# buttonInput.net
KiCad netlist of a schematic drawn in Altium Designer
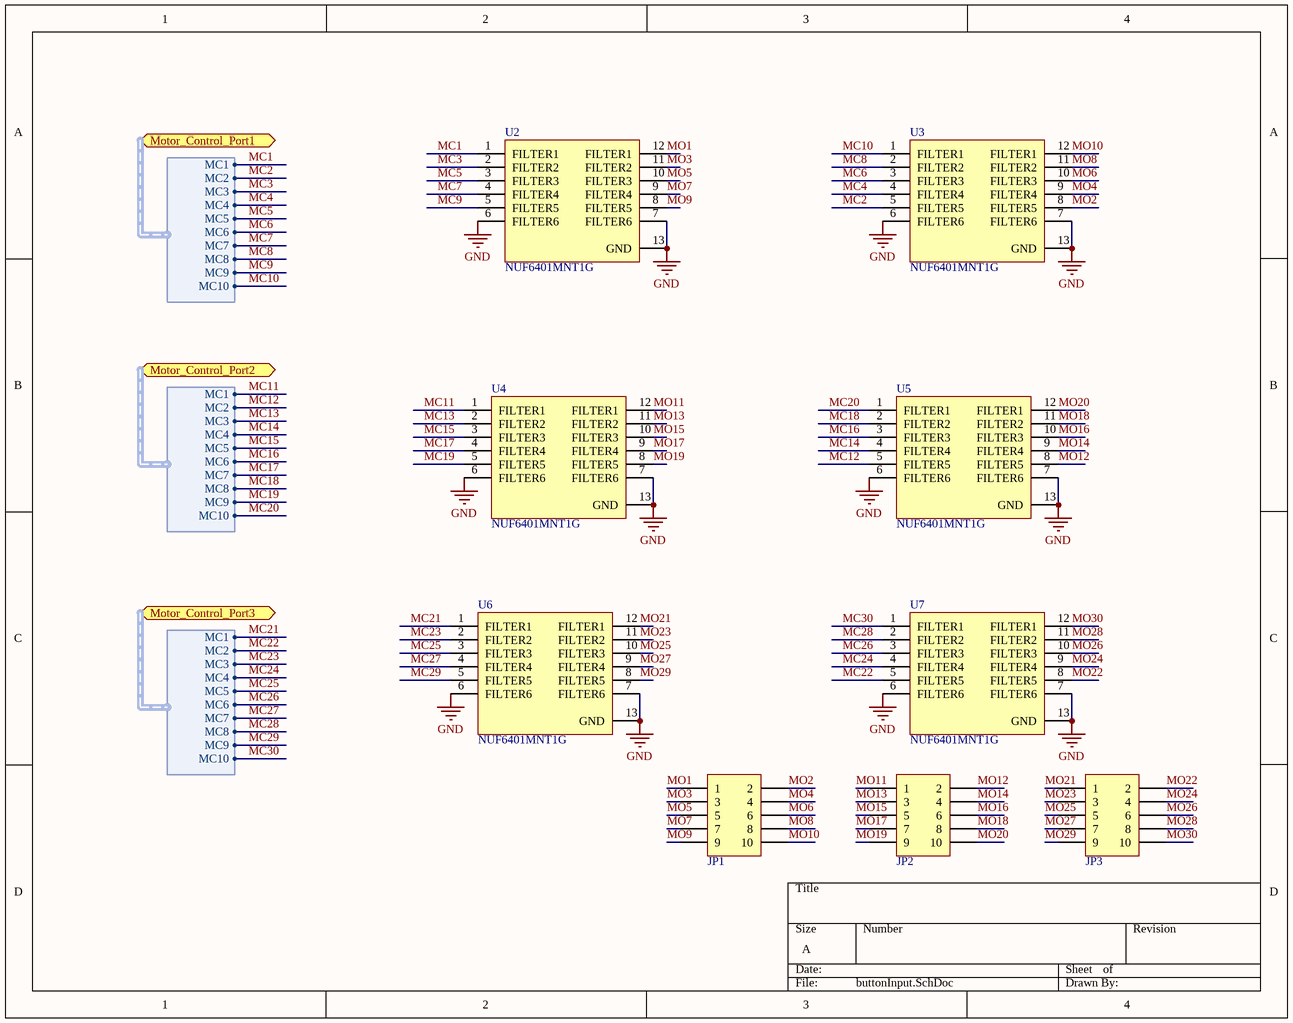
[diagram p0: buttonInput.SchDoc]

(export (version "E")
  (design (tool "Eeschema 10.0.6"))
  (components
    (comp (ref "JP1")
      (value "Header 5x2 2.54mm")
      (footprint "2X5")
      (description "Header, 8-Pin")
      (libsource (lib "HSBNE-Vend") (part "Header 5x2"))
    )
    (comp (ref "JP2")
      (value "Header 5x2 2.54mm")
      (footprint "2X5")
      (description "Header, 8-Pin")
      (libsource (lib "HSBNE-Vend") (part "Header 5x2"))
    )
    (comp (ref "JP3")
      (value "Header 5x2 2.54mm")
      (footprint "2X5")
      (description "Header, 8-Pin")
      (libsource (lib "HSBNE-Vend") (part "Header 5x2"))
    )
    (comp (ref "U2")
      (value "NUF6401MNT1G")
      (footprint "ONSC-DFN-12-506AD-01_V")
      (fields (field (name "MANUFACTURER") "On Semiconductor"))
      (libsource (lib "HSBNE-Vend") (part "CMP-1066-00005-1"))
    )
    (comp (ref "U3")
      (value "NUF6401MNT1G")
      (footprint "ONSC-DFN-12-506AD-01_V")
      (fields (field (name "MANUFACTURER") "On Semiconductor"))
      (libsource (lib "HSBNE-Vend") (part "CMP-1066-00005-1"))
    )
    (comp (ref "U4")
      (value "NUF6401MNT1G")
      (footprint "ONSC-DFN-12-506AD-01_V")
      (fields (field (name "MANUFACTURER") "On Semiconductor"))
      (libsource (lib "HSBNE-Vend") (part "CMP-1066-00005-1"))
    )
    (comp (ref "U5")
      (value "NUF6401MNT1G")
      (footprint "ONSC-DFN-12-506AD-01_V")
      (fields (field (name "MANUFACTURER") "On Semiconductor"))
      (libsource (lib "HSBNE-Vend") (part "CMP-1066-00005-1"))
    )
    (comp (ref "U6")
      (value "NUF6401MNT1G")
      (footprint "ONSC-DFN-12-506AD-01_V")
      (fields (field (name "MANUFACTURER") "On Semiconductor"))
      (libsource (lib "HSBNE-Vend") (part "CMP-1066-00005-1"))
    )
    (comp (ref "U7")
      (value "NUF6401MNT1G")
      (footprint "ONSC-DFN-12-506AD-01_V")
      (fields (field (name "MANUFACTURER") "On Semiconductor"))
      (libsource (lib "HSBNE-Vend") (part "CMP-1066-00005-1"))
    )
  )
  (nets
    (net (code "2") (name "/MC1") (class "Default")
      (node (ref "U2") (pin "1") (pinfunction "FILTER1_1") (pintype "passive"))
    )
    (net (code "3") (name "/MC2") (class "Default")
      (node (ref "U3") (pin "5") (pinfunction "FILTER5_5") (pintype "passive"))
    )
    (net (code "4") (name "/MC3") (class "Default")
      (node (ref "U2") (pin "2") (pinfunction "FILTER2_2") (pintype "passive"))
    )
    (net (code "5") (name "/MC4") (class "Default")
      (node (ref "U3") (pin "4") (pinfunction "FILTER4_4") (pintype "passive"))
    )
    (net (code "6") (name "/MC5") (class "Default")
      (node (ref "U2") (pin "3") (pinfunction "FILTER3_3") (pintype "passive"))
    )
    (net (code "7") (name "/MC6") (class "Default")
      (node (ref "U3") (pin "3") (pinfunction "FILTER3_3") (pintype "passive"))
    )
    (net (code "8") (name "/MC7") (class "Default")
      (node (ref "U2") (pin "4") (pinfunction "FILTER4_4") (pintype "passive"))
    )
    (net (code "9") (name "/MC8") (class "Default")
      (node (ref "U3") (pin "2") (pinfunction "FILTER2_2") (pintype "passive"))
    )
    (net (code "10") (name "/MC9") (class "Default")
      (node (ref "U2") (pin "5") (pinfunction "FILTER5_5") (pintype "passive"))
    )
    (net (code "11") (name "/MC10") (class "Default")
      (node (ref "U3") (pin "1") (pinfunction "FILTER1_1") (pintype "passive"))
    )
    (net (code "12") (name "/MC11") (class "Default")
      (node (ref "U4") (pin "1") (pinfunction "FILTER1_1") (pintype "passive"))
    )
    (net (code "13") (name "/MC12") (class "Default")
      (node (ref "U5") (pin "5") (pinfunction "FILTER5_5") (pintype "passive"))
    )
    (net (code "14") (name "/MC13") (class "Default")
      (node (ref "U4") (pin "2") (pinfunction "FILTER2_2") (pintype "passive"))
    )
    (net (code "15") (name "/MC14") (class "Default")
      (node (ref "U5") (pin "4") (pinfunction "FILTER4_4") (pintype "passive"))
    )
    (net (code "16") (name "/MC15") (class "Default")
      (node (ref "U4") (pin "3") (pinfunction "FILTER3_3") (pintype "passive"))
    )
    (net (code "17") (name "/MC16") (class "Default")
      (node (ref "U5") (pin "3") (pinfunction "FILTER3_3") (pintype "passive"))
    )
    (net (code "18") (name "/MC17") (class "Default")
      (node (ref "U4") (pin "4") (pinfunction "FILTER4_4") (pintype "passive"))
    )
    (net (code "19") (name "/MC18") (class "Default")
      (node (ref "U5") (pin "2") (pinfunction "FILTER2_2") (pintype "passive"))
    )
    (net (code "20") (name "/MC19") (class "Default")
      (node (ref "U4") (pin "5") (pinfunction "FILTER5_5") (pintype "passive"))
    )
    (net (code "21") (name "/MC20") (class "Default")
      (node (ref "U5") (pin "1") (pinfunction "FILTER1_1") (pintype "passive"))
    )
    (net (code "22") (name "/MC21") (class "Default")
      (node (ref "U6") (pin "1") (pinfunction "FILTER1_1") (pintype "passive"))
    )
    (net (code "23") (name "/MC22") (class "Default")
      (node (ref "U7") (pin "5") (pinfunction "FILTER5_5") (pintype "passive"))
    )
    (net (code "24") (name "/MC23") (class "Default")
      (node (ref "U6") (pin "2") (pinfunction "FILTER2_2") (pintype "passive"))
    )
    (net (code "25") (name "/MC24") (class "Default")
      (node (ref "U7") (pin "4") (pinfunction "FILTER4_4") (pintype "passive"))
    )
    (net (code "26") (name "/MC25") (class "Default")
      (node (ref "U6") (pin "3") (pinfunction "FILTER3_3") (pintype "passive"))
    )
    (net (code "27") (name "/MC26") (class "Default")
      (node (ref "U7") (pin "3") (pinfunction "FILTER3_3") (pintype "passive"))
    )
    (net (code "28") (name "/MC27") (class "Default")
      (node (ref "U6") (pin "4") (pinfunction "FILTER4_4") (pintype "passive"))
    )
    (net (code "29") (name "/MC28") (class "Default")
      (node (ref "U7") (pin "2") (pinfunction "FILTER2_2") (pintype "passive"))
    )
    (net (code "30") (name "/MC29") (class "Default")
      (node (ref "U6") (pin "5") (pinfunction "FILTER5_5") (pintype "passive"))
    )
    (net (code "31") (name "/MC30") (class "Default")
      (node (ref "U7") (pin "1") (pinfunction "FILTER1_1") (pintype "passive"))
    )
    (net (code "32") (name "/MO1") (class "Default")
      (node (ref "JP1") (pin "1") (pinfunction "1_1") (pintype "passive"))
      (node (ref "U2") (pin "12") (pinfunction "FILTER1_12") (pintype "passive"))
    )
    (net (code "33") (name "/MO2") (class "Default")
      (node (ref "JP1") (pin "2") (pinfunction "2_2") (pintype "passive"))
      (node (ref "U3") (pin "8") (pinfunction "FILTER5_8") (pintype "passive"))
    )
    (net (code "34") (name "/MO3") (class "Default")
      (node (ref "JP1") (pin "3") (pinfunction "3_3") (pintype "passive"))
      (node (ref "U2") (pin "11") (pinfunction "FILTER2_11") (pintype "passive"))
    )
    (net (code "35") (name "/MO4") (class "Default")
      (node (ref "JP1") (pin "4") (pinfunction "4_4") (pintype "passive"))
      (node (ref "U3") (pin "9") (pinfunction "FILTER4_9") (pintype "passive"))
    )
    (net (code "36") (name "/MO5") (class "Default")
      (node (ref "JP1") (pin "5") (pinfunction "5_5") (pintype "passive"))
      (node (ref "U2") (pin "10") (pinfunction "FILTER3_10") (pintype "passive"))
    )
    (net (code "37") (name "/MO6") (class "Default")
      (node (ref "JP1") (pin "6") (pinfunction "6_6") (pintype "passive"))
      (node (ref "U3") (pin "10") (pinfunction "FILTER3_10") (pintype "passive"))
    )
    (net (code "38") (name "/MO7") (class "Default")
      (node (ref "JP1") (pin "7") (pinfunction "7_7") (pintype "passive"))
      (node (ref "U2") (pin "9") (pinfunction "FILTER4_9") (pintype "passive"))
    )
    (net (code "39") (name "/MO8") (class "Default")
      (node (ref "JP1") (pin "8") (pinfunction "8_8") (pintype "passive"))
      (node (ref "U3") (pin "11") (pinfunction "FILTER2_11") (pintype "passive"))
    )
    (net (code "40") (name "/MO9") (class "Default")
      (node (ref "JP1") (pin "9") (pinfunction "9_9") (pintype "passive"))
      (node (ref "U2") (pin "8") (pinfunction "FILTER5_8") (pintype "passive"))
    )
    (net (code "41") (name "/MO10") (class "Default")
      (node (ref "JP1") (pin "10") (pinfunction "10_10") (pintype "passive"))
      (node (ref "U3") (pin "12") (pinfunction "FILTER1_12") (pintype "passive"))
    )
    (net (code "42") (name "/MO11") (class "Default")
      (node (ref "JP2") (pin "1") (pinfunction "1_1") (pintype "passive"))
      (node (ref "U4") (pin "12") (pinfunction "FILTER1_12") (pintype "passive"))
    )
    (net (code "43") (name "/MO12") (class "Default")
      (node (ref "JP2") (pin "2") (pinfunction "2_2") (pintype "passive"))
      (node (ref "U5") (pin "8") (pinfunction "FILTER5_8") (pintype "passive"))
    )
    (net (code "44") (name "/MO13") (class "Default")
      (node (ref "JP2") (pin "3") (pinfunction "3_3") (pintype "passive"))
      (node (ref "U4") (pin "11") (pinfunction "FILTER2_11") (pintype "passive"))
    )
    (net (code "45") (name "/MO14") (class "Default")
      (node (ref "JP2") (pin "4") (pinfunction "4_4") (pintype "passive"))
      (node (ref "U5") (pin "9") (pinfunction "FILTER4_9") (pintype "passive"))
    )
    (net (code "46") (name "/MO15") (class "Default")
      (node (ref "JP2") (pin "5") (pinfunction "5_5") (pintype "passive"))
      (node (ref "U4") (pin "10") (pinfunction "FILTER3_10") (pintype "passive"))
    )
    (net (code "47") (name "/MO16") (class "Default")
      (node (ref "JP2") (pin "6") (pinfunction "6_6") (pintype "passive"))
      (node (ref "U5") (pin "10") (pinfunction "FILTER3_10") (pintype "passive"))
    )
    (net (code "48") (name "/MO17") (class "Default")
      (node (ref "JP2") (pin "7") (pinfunction "7_7") (pintype "passive"))
      (node (ref "U4") (pin "9") (pinfunction "FILTER4_9") (pintype "passive"))
    )
    (net (code "49") (name "/MO18") (class "Default")
      (node (ref "JP2") (pin "8") (pinfunction "8_8") (pintype "passive"))
      (node (ref "U5") (pin "11") (pinfunction "FILTER2_11") (pintype "passive"))
    )
    (net (code "50") (name "/MO19") (class "Default")
      (node (ref "JP2") (pin "9") (pinfunction "9_9") (pintype "passive"))
      (node (ref "U4") (pin "8") (pinfunction "FILTER5_8") (pintype "passive"))
    )
    (net (code "51") (name "/MO20") (class "Default")
      (node (ref "JP2") (pin "10") (pinfunction "10_10") (pintype "passive"))
      (node (ref "U5") (pin "12") (pinfunction "FILTER1_12") (pintype "passive"))
    )
    (net (code "52") (name "/MO21") (class "Default")
      (node (ref "JP3") (pin "1") (pinfunction "1_1") (pintype "passive"))
      (node (ref "U6") (pin "12") (pinfunction "FILTER1_12") (pintype "passive"))
    )
    (net (code "53") (name "/MO22") (class "Default")
      (node (ref "JP3") (pin "2") (pinfunction "2_2") (pintype "passive"))
      (node (ref "U7") (pin "8") (pinfunction "FILTER5_8") (pintype "passive"))
    )
    (net (code "54") (name "/MO23") (class "Default")
      (node (ref "JP3") (pin "3") (pinfunction "3_3") (pintype "passive"))
      (node (ref "U6") (pin "11") (pinfunction "FILTER2_11") (pintype "passive"))
    )
    (net (code "55") (name "/MO24") (class "Default")
      (node (ref "JP3") (pin "4") (pinfunction "4_4") (pintype "passive"))
      (node (ref "U7") (pin "9") (pinfunction "FILTER4_9") (pintype "passive"))
    )
    (net (code "56") (name "/MO25") (class "Default")
      (node (ref "JP3") (pin "5") (pinfunction "5_5") (pintype "passive"))
      (node (ref "U6") (pin "10") (pinfunction "FILTER3_10") (pintype "passive"))
    )
    (net (code "57") (name "/MO26") (class "Default")
      (node (ref "JP3") (pin "6") (pinfunction "6_6") (pintype "passive"))
      (node (ref "U7") (pin "10") (pinfunction "FILTER3_10") (pintype "passive"))
    )
    (net (code "58") (name "/MO27") (class "Default")
      (node (ref "JP3") (pin "7") (pinfunction "7_7") (pintype "passive"))
      (node (ref "U6") (pin "9") (pinfunction "FILTER4_9") (pintype "passive"))
    )
    (net (code "59") (name "/MO28") (class "Default")
      (node (ref "JP3") (pin "8") (pinfunction "8_8") (pintype "passive"))
      (node (ref "U7") (pin "11") (pinfunction "FILTER2_11") (pintype "passive"))
    )
    (net (code "60") (name "/MO29") (class "Default")
      (node (ref "JP3") (pin "9") (pinfunction "9_9") (pintype "passive"))
      (node (ref "U6") (pin "8") (pinfunction "FILTER5_8") (pintype "passive"))
    )
    (net (code "61") (name "/MO30") (class "Default")
      (node (ref "JP3") (pin "10") (pinfunction "10_10") (pintype "passive"))
      (node (ref "U7") (pin "12") (pinfunction "FILTER1_12") (pintype "passive"))
    )
    (net (code "63") (name "GND") (class "Default")
      (node (ref "U2") (pin "13") (pinfunction "GND_13") (pintype "power_in"))
      (node (ref "U2") (pin "6") (pinfunction "FILTER6_6") (pintype "passive"))
      (node (ref "U2") (pin "7") (pinfunction "FILTER6_7") (pintype "passive"))
      (node (ref "U3") (pin "13") (pinfunction "GND_13") (pintype "power_in"))
      (node (ref "U3") (pin "6") (pinfunction "FILTER6_6") (pintype "passive"))
      (node (ref "U3") (pin "7") (pinfunction "FILTER6_7") (pintype "passive"))
      (node (ref "U4") (pin "13") (pinfunction "GND_13") (pintype "power_in"))
      (node (ref "U4") (pin "6") (pinfunction "FILTER6_6") (pintype "passive"))
      (node (ref "U4") (pin "7") (pinfunction "FILTER6_7") (pintype "passive"))
      (node (ref "U5") (pin "13") (pinfunction "GND_13") (pintype "power_in"))
      (node (ref "U5") (pin "6") (pinfunction "FILTER6_6") (pintype "passive"))
      (node (ref "U5") (pin "7") (pinfunction "FILTER6_7") (pintype "passive"))
      (node (ref "U6") (pin "13") (pinfunction "GND_13") (pintype "power_in"))
      (node (ref "U6") (pin "6") (pinfunction "FILTER6_6") (pintype "passive"))
      (node (ref "U6") (pin "7") (pinfunction "FILTER6_7") (pintype "passive"))
      (node (ref "U7") (pin "13") (pinfunction "GND_13") (pintype "power_in"))
      (node (ref "U7") (pin "6") (pinfunction "FILTER6_6") (pintype "passive"))
      (node (ref "U7") (pin "7") (pinfunction "FILTER6_7") (pintype "passive"))
    )
  )
)
